# Micro.net
KiCad netlist of a schematic drawn in Altium Designer
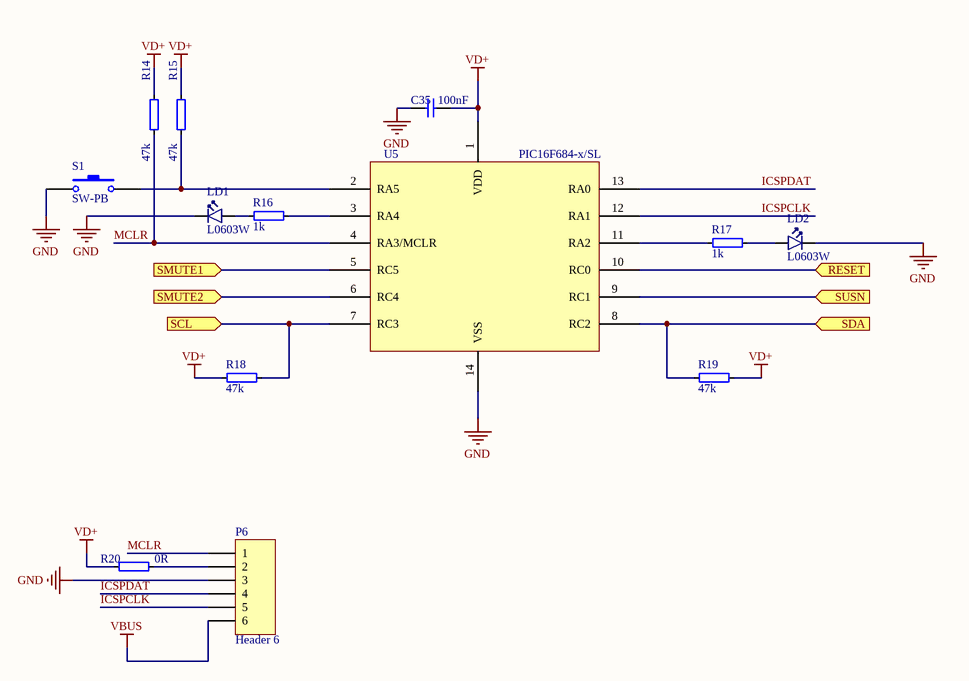
[diagram p0: Micro.SchDoc]

(export (version "E")
  (design (tool "Eeschema 10.0.6"))
  (components
    (comp (ref "C35")
      (value "100nF")
      (footprint "0402s")
      (description "Chip Cap 0402")
      (fields (field (name "PART NUMBER") "C0402-100n") (field (name "PUBLISHER") "Nordic Semiconductor"))
      (libsource (lib "Nordic Passive DB") (part "CAP"))
    )
    (comp (ref "LD1")
      (value "L0603W")
      (footprint "LED_0603")
      (description "LED 0603, 19-213/W1D")
      (fields
        (field (name "PART NUMBER") "19-213/W1D")
        (field (name "MANUFACTURER") "Everlight")
        (field (name "PUBLISHER") "Nordic Semiconductor")
      )
      (libsource (lib "Nordic Discrete DB") (part "D{colon}LED"))
    )
    (comp (ref "LD2")
      (value "L0603W")
      (footprint "LED_0603")
      (description "LED 0603, 19-213/W1D")
      (fields
        (field (name "PART NUMBER") "19-213/W1D")
        (field (name "MANUFACTURER") "Everlight")
        (field (name "PUBLISHER") "Nordic Semiconductor")
      )
      (libsource (lib "Nordic Discrete DB") (part "D{colon}LED"))
    )
    (comp (ref "P6")
      (value "Header 6")
      (footprint "HDR1X6")
      (description "Header, 6-Pin")
      (fields (field (name "PUBLISHER") "Altium Limited"))
      (libsource (lib "Miscellaneous Connectors") (part "Header 6"))
    )
    (comp (ref "R14")
      (value "47k")
      (footprint "0402s")
      (description "Chip Res 0402")
      (fields (field (name "PART NUMBER") "R0402-47k") (field (name "PUBLISHER") "Nordic Semiconductor"))
      (libsource (lib "Nordic Passive DB") (part "RES_1"))
    )
    (comp (ref "R15")
      (value "47k")
      (footprint "0402s")
      (description "Chip Res 0402")
      (fields (field (name "PART NUMBER") "R0402-47k") (field (name "PUBLISHER") "Nordic Semiconductor"))
      (libsource (lib "Nordic Passive DB") (part "RES_1"))
    )
    (comp (ref "R16")
      (value "1k")
      (footprint "0402s")
      (description "Chip Res 0402")
      (fields (field (name "PART NUMBER") "R0402-1k0") (field (name "PUBLISHER") "Nordic Semiconductor"))
      (libsource (lib "Nordic Passive DB") (part "RES_1"))
    )
    (comp (ref "R17")
      (value "1k")
      (footprint "0402s")
      (description "Chip Res 0402")
      (fields (field (name "PART NUMBER") "R0402-1k0") (field (name "PUBLISHER") "Nordic Semiconductor"))
      (libsource (lib "Nordic Passive DB") (part "RES_1"))
    )
    (comp (ref "R18")
      (value "47k")
      (footprint "0402s")
      (description "Chip Res 0402")
      (fields (field (name "PART NUMBER") "R0402-47k") (field (name "PUBLISHER") "Nordic Semiconductor"))
      (libsource (lib "Nordic Passive DB") (part "RES_1"))
    )
    (comp (ref "R19")
      (value "47k")
      (footprint "0402s")
      (description "Chip Res 0402")
      (fields (field (name "PART NUMBER") "R0402-47k") (field (name "PUBLISHER") "Nordic Semiconductor"))
      (libsource (lib "Nordic Passive DB") (part "RES_1"))
    )
    (comp (ref "R20")
      (value "0R")
      (footprint "0402s")
      (description "Chip Res 0402")
      (fields (field (name "PART NUMBER") "R0402-0R") (field (name "PUBLISHER") "Nordic Semiconductor"))
      (libsource (lib "Nordic Passive DB") (part "RES_1"))
    )
    (comp (ref "S1")
      (value "SW-PB")
      (footprint "E-Switch")
      (description "Switch")
      (fields (field (name "PUBLISHER") "Altium Limited"))
      (libsource (lib "Miscellaneous Devices") (part "SW-PB"))
    )
    (comp (ref "U5")
      (value "PIC16F684-x/SL")
      (footprint "TSOP65P640X120-14N")
      (libsource (lib "nRF2460") (part "PIC16F684-x/SL"))
    )
  )
  (nets
    (net (code "1") (name "/ICSPCLK") (class "Default")
      (node (ref "P6") (pin "5") (pinfunction "5_5") (pintype "passive"))
      (node (ref "U5") (pin "12") (pinfunction "RA1_12") (pintype "passive"))
    )
    (net (code "2") (name "/ICSPDAT") (class "Default")
      (node (ref "P6") (pin "4") (pinfunction "4_4") (pintype "passive"))
      (node (ref "U5") (pin "13") (pinfunction "RA0_13") (pintype "passive"))
    )
    (net (code "3") (name "/MCLR") (class "Default")
      (node (ref "P6") (pin "1") (pinfunction "1_1") (pintype "passive"))
      (node (ref "R14") (pin "1") (pinfunction "1_1") (pintype "passive"))
      (node (ref "U5") (pin "4") (pinfunction "RA3/MCLR_4") (pintype "passive"))
    )
    (net (code "4") (name "/RESET") (class "Default")
      (node (ref "U5") (pin "10") (pinfunction "RC0_10") (pintype "passive"))
    )
    (net (code "5") (name "/SCL") (class "Default")
      (node (ref "R18") (pin "2") (pinfunction "2_2") (pintype "passive"))
      (node (ref "U5") (pin "7") (pinfunction "RC3_7") (pintype "passive"))
    )
    (net (code "6") (name "/SDA") (class "Default")
      (node (ref "R19") (pin "2") (pinfunction "2_2") (pintype "passive"))
      (node (ref "U5") (pin "8") (pinfunction "RC2_8") (pintype "passive"))
    )
    (net (code "7") (name "/SMUTE1") (class "Default")
      (node (ref "U5") (pin "5") (pinfunction "RC5_5") (pintype "passive"))
    )
    (net (code "8") (name "/SMUTE2") (class "Default")
      (node (ref "U5") (pin "6") (pinfunction "RC4_6") (pintype "passive"))
    )
    (net (code "9") (name "/SUSN") (class "Default")
      (node (ref "U5") (pin "9") (pinfunction "RC1_9") (pintype "passive"))
    )
    (net (code "10") (name "GND") (class "Default")
      (node (ref "C35") (pin "1") (pinfunction "1_1") (pintype "passive"))
      (node (ref "LD1") (pin "1") (pinfunction "C_1") (pintype "passive"))
      (node (ref "LD2") (pin "1") (pinfunction "C_1") (pintype "passive"))
      (node (ref "P6") (pin "3") (pinfunction "3_3") (pintype "passive"))
      (node (ref "S1") (pin "1") (pinfunction "1_1") (pintype "passive"))
      (node (ref "U5") (pin "14") (pinfunction "VSS_14") (pintype "passive"))
    )
    (net (code "11") (name "Net-(LD1-A)") (class "Default")
      (node (ref "LD1") (pin "2") (pinfunction "A_2") (pintype "passive"))
      (node (ref "R16") (pin "2") (pinfunction "2_2") (pintype "passive"))
    )
    (net (code "12") (name "Net-(LD2-A)") (class "Default")
      (node (ref "LD2") (pin "2") (pinfunction "A_2") (pintype "passive"))
      (node (ref "R17") (pin "2") (pinfunction "2_2") (pintype "passive"))
    )
    (net (code "13") (name "Net-(P6-Pad2)") (class "Default")
      (node (ref "P6") (pin "2") (pinfunction "2_2") (pintype "passive"))
      (node (ref "R20") (pin "2") (pinfunction "2_2") (pintype "passive"))
    )
    (net (code "14") (name "Net-(U5-RA2)") (class "Default")
      (node (ref "R17") (pin "1") (pinfunction "1_1") (pintype "passive"))
      (node (ref "U5") (pin "11") (pinfunction "RA2_11") (pintype "passive"))
    )
    (net (code "15") (name "Net-(U5-RA4)") (class "Default")
      (node (ref "R16") (pin "1") (pinfunction "1_1") (pintype "passive"))
      (node (ref "U5") (pin "3") (pinfunction "RA4_3") (pintype "passive"))
    )
    (net (code "16") (name "Net-(U5-RA5)") (class "Default")
      (node (ref "R15") (pin "1") (pinfunction "1_1") (pintype "passive"))
      (node (ref "S1") (pin "2") (pinfunction "2_2") (pintype "passive"))
      (node (ref "U5") (pin "2") (pinfunction "RA5_2") (pintype "passive"))
    )
    (net (code "17") (name "VBUS") (class "Default")
      (node (ref "P6") (pin "6") (pinfunction "6_6") (pintype "passive"))
    )
    (net (code "18") (name "VD+") (class "Default")
      (node (ref "C35") (pin "2") (pinfunction "2_2") (pintype "passive"))
      (node (ref "R14") (pin "2") (pinfunction "2_2") (pintype "passive"))
      (node (ref "R15") (pin "2") (pinfunction "2_2") (pintype "passive"))
      (node (ref "R18") (pin "1") (pinfunction "1_1") (pintype "passive"))
      (node (ref "R19") (pin "1") (pinfunction "1_1") (pintype "passive"))
      (node (ref "R20") (pin "1") (pinfunction "1_1") (pintype "passive"))
      (node (ref "U5") (pin "1") (pinfunction "VDD_1") (pintype "passive"))
    )
  )
)
